# rt1_handle.net
KiCad netlist of a schematic drawn in EAGLE
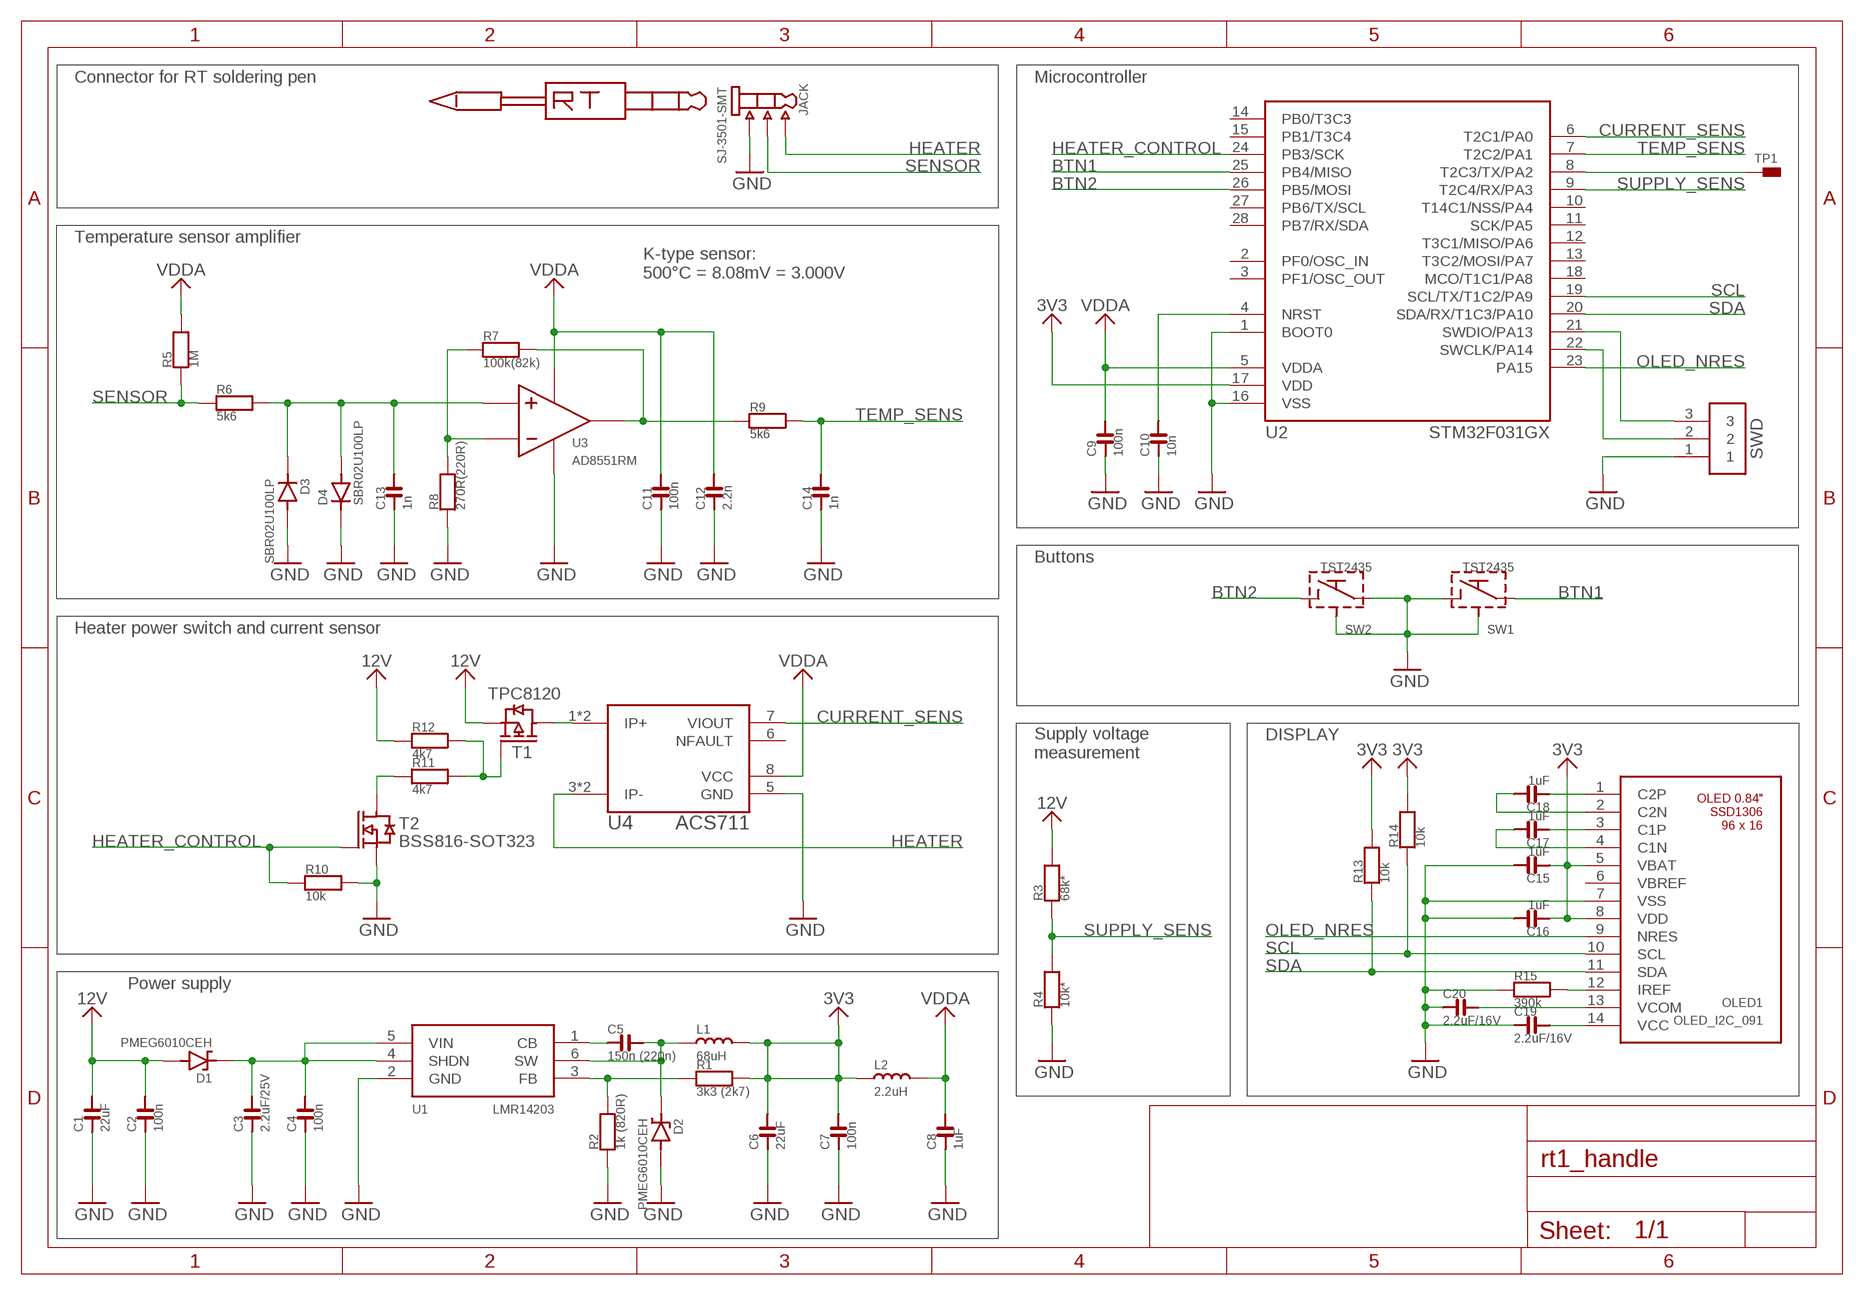
[diagram p0: schematic, sheet 1]

(export (version "E")
  (design (tool "Eeschema 10.0.6"))
  (components
    (comp (ref "C1")
      (value "22uF")
      (footprint "eagle-import:1206")
      (libsource (lib "eagle-import") (part "C1206"))
    )
    (comp (ref "C2")
      (value "100n")
      (footprint "eagle-import:0402")
      (libsource (lib "eagle-import") (part "C0402"))
    )
    (comp (ref "C3")
      (value "2.2uF/25V")
      (footprint "eagle-import:0805")
      (libsource (lib "eagle-import") (part "C0805"))
    )
    (comp (ref "C4")
      (value "100n")
      (footprint "eagle-import:0402")
      (libsource (lib "eagle-import") (part "C0402"))
    )
    (comp (ref "C5")
      (value "150n (220n)")
      (footprint "eagle-import:0402")
      (libsource (lib "eagle-import") (part "C0402"))
    )
    (comp (ref "C6")
      (value "22uF")
      (footprint "eagle-import:0805")
      (libsource (lib "eagle-import") (part "C0805"))
    )
    (comp (ref "C7")
      (value "100n")
      (footprint "eagle-import:0402")
      (libsource (lib "eagle-import") (part "C0402"))
    )
    (comp (ref "C8")
      (value "1uF")
      (footprint "eagle-import:0603")
      (libsource (lib "eagle-import") (part "C0603"))
    )
    (comp (ref "C9")
      (value "100n")
      (footprint "eagle-import:0402")
      (libsource (lib "eagle-import") (part "C0402"))
    )
    (comp (ref "C10")
      (value "10n")
      (footprint "eagle-import:0402")
      (libsource (lib "eagle-import") (part "C0402"))
    )
    (comp (ref "C11")
      (value "100n")
      (footprint "eagle-import:0402")
      (libsource (lib "eagle-import") (part "C0402"))
    )
    (comp (ref "C12")
      (value "2.2n")
      (footprint "eagle-import:0603")
      (libsource (lib "eagle-import") (part "C0603"))
    )
    (comp (ref "C13")
      (value "1n")
      (footprint "eagle-import:0402")
      (libsource (lib "eagle-import") (part "C0402"))
    )
    (comp (ref "C14")
      (value "1n")
      (footprint "eagle-import:0402")
      (libsource (lib "eagle-import") (part "C0402"))
    )
    (comp (ref "C15")
      (value "1uF")
      (footprint "eagle-import:0603")
      (libsource (lib "eagle-import") (part "C0603"))
    )
    (comp (ref "C16")
      (value "1uF")
      (footprint "eagle-import:0603")
      (libsource (lib "eagle-import") (part "C0603"))
    )
    (comp (ref "C17")
      (value "1uF")
      (footprint "eagle-import:0603")
      (libsource (lib "eagle-import") (part "C0603"))
    )
    (comp (ref "C18")
      (value "1uF")
      (footprint "eagle-import:0603")
      (libsource (lib "eagle-import") (part "C0603"))
    )
    (comp (ref "C19")
      (value "2.2uF/16V")
      (footprint "eagle-import:0603")
      (libsource (lib "eagle-import") (part "C0603"))
    )
    (comp (ref "C20")
      (value "2.2uF/16V")
      (footprint "eagle-import:0603")
      (libsource (lib "eagle-import") (part "C0603"))
    )
    (comp (ref "D1")
      (value "PMEG6010CEH")
      (footprint "eagle-import:SOD123F")
      (libsource (lib "eagle-import") (part "PMEG6010CEH"))
    )
    (comp (ref "D2")
      (value "PMEG6010CEH")
      (footprint "eagle-import:SOD123F")
      (libsource (lib "eagle-import") (part "PMEG6010CEH"))
    )
    (comp (ref "D3")
      (value "SBR02U100LP")
      (footprint "eagle-import:DFN1006")
      (libsource (lib "eagle-import") (part "SBR02U100LP"))
    )
    (comp (ref "D4")
      (value "SBR02U100LP")
      (footprint "eagle-import:DFN1006")
      (libsource (lib "eagle-import") (part "SBR02U100LP"))
    )
    (comp (ref "JACK")
      (value "SJ-3501-SMT")
      (footprint "eagle-import:SJ-3501-SMT")
      (libsource (lib "eagle-import") (part "SJ-3501-SMT"))
    )
    (comp (ref "L1")
      (value "68uH")
      (footprint "eagle-import:1717")
      (libsource (lib "eagle-import") (part "L1717"))
    )
    (comp (ref "L2")
      (value "2.2uH")
      (footprint "eagle-import:0805")
      (libsource (lib "eagle-import") (part "L0805"))
    )
    (comp (ref "OLED1")
      (value "OLED_I2C_091")
      (footprint "eagle-import:OLED_I2C_091")
      (libsource (lib "eagle-import") (part "OLED_I2C_091"))
    )
    (comp (ref "R1")
      (value "3k3 (2k7)")
      (footprint "eagle-import:0402")
      (libsource (lib "eagle-import") (part "R0402"))
    )
    (comp (ref "R2")
      (value "1k (820R)")
      (footprint "eagle-import:0402")
      (libsource (lib "eagle-import") (part "R0402"))
    )
    (comp (ref "R3")
      (value "68k*")
      (footprint "eagle-import:0402")
      (libsource (lib "eagle-import") (part "R0402"))
    )
    (comp (ref "R4")
      (value "10k*")
      (footprint "eagle-import:0402")
      (libsource (lib "eagle-import") (part "R0402"))
    )
    (comp (ref "R5")
      (value "1M")
      (footprint "eagle-import:0402")
      (libsource (lib "eagle-import") (part "R0402"))
    )
    (comp (ref "R6")
      (value "5k6")
      (footprint "eagle-import:0402")
      (libsource (lib "eagle-import") (part "R0402"))
    )
    (comp (ref "R7")
      (value "100k(82k)")
      (footprint "eagle-import:0402")
      (libsource (lib "eagle-import") (part "R0402"))
    )
    (comp (ref "R8")
      (value "270R(220R)")
      (footprint "eagle-import:0402")
      (libsource (lib "eagle-import") (part "R0402"))
    )
    (comp (ref "R9")
      (value "5k6")
      (footprint "eagle-import:0402")
      (libsource (lib "eagle-import") (part "R0402"))
    )
    (comp (ref "R10")
      (value "10k")
      (footprint "eagle-import:0402")
      (libsource (lib "eagle-import") (part "R0402"))
    )
    (comp (ref "R11")
      (value "4k7")
      (footprint "eagle-import:0402")
      (libsource (lib "eagle-import") (part "R0402"))
    )
    (comp (ref "R12")
      (value "4k7")
      (footprint "eagle-import:0402")
      (libsource (lib "eagle-import") (part "R0402"))
    )
    (comp (ref "R13")
      (value "10k")
      (footprint "eagle-import:0402")
      (libsource (lib "eagle-import") (part "R0402"))
    )
    (comp (ref "R14")
      (value "10k")
      (footprint "eagle-import:0402")
      (libsource (lib "eagle-import") (part "R0402"))
    )
    (comp (ref "R15")
      (value "390k")
      (footprint "eagle-import:0402")
      (libsource (lib "eagle-import") (part "R0402"))
    )
    (comp (ref "RT")
      (value "RT-1")
      (footprint "eagle-import:RT-1")
      (libsource (lib "eagle-import") (part "RT-1"))
    )
    (comp (ref "SW1")
      (value "TST2435")
      (footprint "eagle-import:TST2435")
      (libsource (lib "eagle-import") (part "TST2435"))
    )
    (comp (ref "SW2")
      (value "TST2435")
      (footprint "eagle-import:TST2435")
      (libsource (lib "eagle-import") (part "TST2435"))
    )
    (comp (ref "SWD")
      (value "PINHEAD1X3X")
      (footprint "eagle-import:PIN1X3")
      (libsource (lib "eagle-import") (part "PINHEAD1X3X"))
    )
    (comp (ref "T1")
      (value "TPC8120")
      (footprint "eagle-import:SOIC8")
      (libsource (lib "eagle-import") (part "TPC8120"))
    )
    (comp (ref "T2")
      (value "BSS816-SOT323")
      (footprint "eagle-import:SOT23")
      (libsource (lib "eagle-import") (part "IRLML2502"))
    )
    (comp (ref "TP1")
      (value "TEST_PAD15X60")
      (footprint "eagle-import:SMD_15_60")
      (libsource (lib "eagle-import") (part "TEST_PAD15X60"))
    )
    (comp (ref "U1")
      (value "LMR14203")
      (footprint "eagle-import:SOT23-6")
      (libsource (lib "eagle-import") (part "LMR14203"))
    )
    (comp (ref "U2")
      (value "STM32F031GX")
      (footprint "eagle-import:UFQFPN28")
      (libsource (lib "eagle-import") (part "STM32F031GX"))
    )
    (comp (ref "U3")
      (value "AD8551RM")
      (footprint "eagle-import:MSOP8")
      (libsource (lib "eagle-import") (part "AD8551RM"))
    )
    (comp (ref "U4")
      (value "ACS711")
      (footprint "eagle-import:SOIC8")
      (libsource (lib "eagle-import") (part "ACS711"))
    )
  )
  (nets
    (net (code "1") (name "/BTN1") (class "Default")
      (node (ref "SW1") (pin "1") (pinfunction "1_1") (pintype "passive"))
      (node (ref "U2") (pin "25") (pinfunction "PB4/MISO_25") (pintype "bidirectional"))
    )
    (net (code "2") (name "/BTN2") (class "Default")
      (node (ref "SW2") (pin "2") (pinfunction "2_2") (pintype "passive"))
      (node (ref "U2") (pin "26") (pinfunction "PB5/MOSI_26") (pintype "bidirectional"))
    )
    (net (code "3") (name "/CURRENT_SENS") (class "Default")
      (node (ref "U2") (pin "6") (pinfunction "T2C1/PA0_6") (pintype "bidirectional"))
      (node (ref "U4") (pin "7") (pinfunction "VIOUT_7") (pintype "bidirectional"))
    )
    (net (code "4") (name "/HEATER") (class "Default")
      (node (ref "JACK") (pin "2") (pinfunction "2_2") (pintype "bidirectional"))
      (node (ref "JACK") (pin "4") (pinfunction "2_4") (pintype "bidirectional"))
      (node (ref "U4") (pin "3") (pinfunction "IP-_3") (pintype "bidirectional"))
      (node (ref "U4") (pin "4") (pinfunction "IP-_4") (pintype "bidirectional"))
    )
    (net (code "5") (name "/HEATER_CONTROL") (class "Default")
      (node (ref "R10") (pin "1") (pinfunction "1_1") (pintype "passive"))
      (node (ref "T2") (pin "1") (pinfunction "G_1") (pintype "bidirectional"))
      (node (ref "U2") (pin "24") (pinfunction "PB3/SCK_24") (pintype "bidirectional"))
    )
    (net (code "6") (name "/OLED_NRES") (class "Default")
      (node (ref "OLED1") (pin "9") (pinfunction "NRES_9") (pintype "input"))
      (node (ref "U2") (pin "23") (pinfunction "PA15_23") (pintype "bidirectional"))
    )
    (net (code "7") (name "/SCL") (class "Default")
      (node (ref "OLED1") (pin "10") (pinfunction "SCL_10") (pintype "input"))
      (node (ref "R14") (pin "1") (pinfunction "1_1") (pintype "passive"))
      (node (ref "U2") (pin "19") (pinfunction "SCL/TX/T1C2/PA9_19") (pintype "bidirectional"))
    )
    (net (code "8") (name "/SDA") (class "Default")
      (node (ref "OLED1") (pin "11") (pinfunction "SDA_11") (pintype "input"))
      (node (ref "R13") (pin "1") (pinfunction "1_1") (pintype "passive"))
      (node (ref "U2") (pin "20") (pinfunction "SDA/RX/T1C3/PA10_20") (pintype "bidirectional"))
    )
    (net (code "9") (name "/SENSOR") (class "Default")
      (node (ref "JACK") (pin "3") (pinfunction "3_3") (pintype "bidirectional"))
      (node (ref "R5") (pin "1") (pinfunction "1_1") (pintype "passive"))
      (node (ref "R6") (pin "1") (pinfunction "1_1") (pintype "passive"))
    )
    (net (code "10") (name "/SUPPLY_SENS") (class "Default")
      (node (ref "R3") (pin "1") (pinfunction "1_1") (pintype "passive"))
      (node (ref "R4") (pin "2") (pinfunction "2_2") (pintype "passive"))
      (node (ref "U2") (pin "9") (pinfunction "T2C4/RX/PA3_9") (pintype "bidirectional"))
    )
    (net (code "11") (name "/TEMP_SENS") (class "Default")
      (node (ref "C14") (pin "2") (pinfunction "2_2") (pintype "passive"))
      (node (ref "R9") (pin "2") (pinfunction "2_2") (pintype "passive"))
      (node (ref "U2") (pin "7") (pinfunction "T2C2/PA1_7") (pintype "bidirectional"))
    )
    (net (code "12") (name "3V3") (class "Default")
      (node (ref "C15") (pin "1") (pinfunction "1_1") (pintype "passive"))
      (node (ref "C16") (pin "1") (pinfunction "1_1") (pintype "passive"))
      (node (ref "C6") (pin "2") (pinfunction "2_2") (pintype "passive"))
      (node (ref "C7") (pin "2") (pinfunction "2_2") (pintype "passive"))
      (node (ref "L1") (pin "2") (pinfunction "2_2") (pintype "passive"))
      (node (ref "L2") (pin "1") (pinfunction "1_1") (pintype "passive"))
      (node (ref "OLED1") (pin "5") (pinfunction "VBAT_5") (pintype "power_in"))
      (node (ref "OLED1") (pin "8") (pinfunction "VDD_8") (pintype "power_in"))
      (node (ref "R1") (pin "2") (pinfunction "2_2") (pintype "passive"))
      (node (ref "R13") (pin "2") (pinfunction "2_2") (pintype "passive"))
      (node (ref "R14") (pin "2") (pinfunction "2_2") (pintype "passive"))
      (node (ref "U2") (pin "17") (pinfunction "VDD_17") (pintype "power_in"))
    )
    (net (code "13") (name "12V") (class "Default")
      (node (ref "C1") (pin "2") (pinfunction "2_2") (pintype "passive"))
      (node (ref "C2") (pin "2") (pinfunction "2_2") (pintype "passive"))
      (node (ref "D1") (pin "A") (pinfunction "A_A") (pintype "passive"))
      (node (ref "R12") (pin "1") (pinfunction "1_1") (pintype "passive"))
      (node (ref "R3") (pin "2") (pinfunction "2_2") (pintype "passive"))
      (node (ref "T1") (pin "1") (pinfunction "S_1") (pintype "bidirectional"))
      (node (ref "T1") (pin "2") (pinfunction "S_2") (pintype "bidirectional"))
      (node (ref "T1") (pin "3") (pinfunction "S_3") (pintype "bidirectional"))
    )
    (net (code "14") (name "GND") (class "Default")
      (node (ref "C1") (pin "1") (pinfunction "1_1") (pintype "passive"))
      (node (ref "C10") (pin "1") (pinfunction "1_1") (pintype "passive"))
      (node (ref "C11") (pin "1") (pinfunction "1_1") (pintype "passive"))
      (node (ref "C12") (pin "1") (pinfunction "1_1") (pintype "passive"))
      (node (ref "C13") (pin "1") (pinfunction "1_1") (pintype "passive"))
      (node (ref "C14") (pin "1") (pinfunction "1_1") (pintype "passive"))
      (node (ref "C15") (pin "2") (pinfunction "2_2") (pintype "passive"))
      (node (ref "C16") (pin "2") (pinfunction "2_2") (pintype "passive"))
      (node (ref "C19") (pin "1") (pinfunction "1_1") (pintype "passive"))
      (node (ref "C2") (pin "1") (pinfunction "1_1") (pintype "passive"))
      (node (ref "C20") (pin "1") (pinfunction "1_1") (pintype "passive"))
      (node (ref "C3") (pin "1") (pinfunction "1_1") (pintype "passive"))
      (node (ref "C4") (pin "1") (pinfunction "1_1") (pintype "passive"))
      (node (ref "C6") (pin "1") (pinfunction "1_1") (pintype "passive"))
      (node (ref "C7") (pin "1") (pinfunction "1_1") (pintype "passive"))
      (node (ref "C8") (pin "1") (pinfunction "1_1") (pintype "passive"))
      (node (ref "C9") (pin "1") (pinfunction "1_1") (pintype "passive"))
      (node (ref "D2") (pin "A") (pinfunction "A_A") (pintype "passive"))
      (node (ref "D3") (pin "A") (pinfunction "A_A") (pintype "passive"))
      (node (ref "D4") (pin "C") (pinfunction "C_C") (pintype "passive"))
      (node (ref "JACK") (pin "1") (pinfunction "1_1") (pintype "bidirectional"))
      (node (ref "JACK") (pin "5") (pinfunction "1_5") (pintype "bidirectional"))
      (node (ref "OLED1") (pin "7") (pinfunction "VSS_7") (pintype "power_in"))
      (node (ref "R10") (pin "2") (pinfunction "2_2") (pintype "passive"))
      (node (ref "R15") (pin "1") (pinfunction "1_1") (pintype "passive"))
      (node (ref "R2") (pin "1") (pinfunction "1_1") (pintype "passive"))
      (node (ref "R4") (pin "1") (pinfunction "1_1") (pintype "passive"))
      (node (ref "R8") (pin "1") (pinfunction "1_1") (pintype "passive"))
      (node (ref "SW1") (pin "2") (pinfunction "2_2") (pintype "passive"))
      (node (ref "SW1") (pin "EP1") (pinfunction "SHIELD_EP1") (pintype "passive"))
      (node (ref "SW1") (pin "EP2") (pinfunction "SHIELD_EP2") (pintype "passive"))
      (node (ref "SW2") (pin "1") (pinfunction "1_1") (pintype "passive"))
      (node (ref "SW2") (pin "EP1") (pinfunction "SHIELD_EP1") (pintype "passive"))
      (node (ref "SW2") (pin "EP2") (pinfunction "SHIELD_EP2") (pintype "passive"))
      (node (ref "SWD") (pin "1") (pinfunction "1_1") (pintype "bidirectional"))
      (node (ref "T2") (pin "2") (pinfunction "S_2") (pintype "bidirectional"))
      (node (ref "U1") (pin "2") (pinfunction "GND_2") (pintype "power_in"))
      (node (ref "U2") (pin "1") (pinfunction "BOOT0_1") (pintype "input"))
      (node (ref "U2") (pin "16") (pinfunction "VSS_16") (pintype "power_in"))
      (node (ref "U3") (pin "4") (pinfunction "V-_4") (pintype "power_in"))
      (node (ref "U4") (pin "5") (pinfunction "GND_5") (pintype "power_in"))
    )
    (net (code "15") (name "Net-(OLED1-C1N)") (class "Default")
      (node (ref "C17") (pin "2") (pinfunction "2_2") (pintype "passive"))
      (node (ref "OLED1") (pin "4") (pinfunction "C1N_4") (pintype "passive"))
    )
    (net (code "16") (name "Net-(OLED1-C1P)") (class "Default")
      (node (ref "C17") (pin "1") (pinfunction "1_1") (pintype "passive"))
      (node (ref "OLED1") (pin "3") (pinfunction "C1P_3") (pintype "passive"))
    )
    (net (code "17") (name "Net-(OLED1-C2N)") (class "Default")
      (node (ref "C18") (pin "2") (pinfunction "2_2") (pintype "passive"))
      (node (ref "OLED1") (pin "2") (pinfunction "C2N_2") (pintype "passive"))
    )
    (net (code "18") (name "Net-(OLED1-C2P)") (class "Default")
      (node (ref "C18") (pin "1") (pinfunction "1_1") (pintype "passive"))
      (node (ref "OLED1") (pin "1") (pinfunction "C2P_1") (pintype "passive"))
    )
    (net (code "19") (name "Net-(OLED1-IREF)") (class "Default")
      (node (ref "OLED1") (pin "12") (pinfunction "IREF_12") (pintype "passive"))
      (node (ref "R15") (pin "2") (pinfunction "2_2") (pintype "passive"))
    )
    (net (code "20") (name "Net-(OLED1-VCC)") (class "Default")
      (node (ref "C19") (pin "2") (pinfunction "2_2") (pintype "passive"))
      (node (ref "OLED1") (pin "14") (pinfunction "VCC_14") (pintype "power_in"))
    )
    (net (code "21") (name "Net-(OLED1-VCOM)") (class "Default")
      (node (ref "C20") (pin "2") (pinfunction "2_2") (pintype "passive"))
      (node (ref "OLED1") (pin "13") (pinfunction "VCOM_13") (pintype "passive"))
    )
    (net (code "22") (name "Net-(T1-D-Pad5)") (class "Default")
      (node (ref "T1") (pin "5") (pinfunction "D_5") (pintype "bidirectional"))
      (node (ref "T1") (pin "6") (pinfunction "D_6") (pintype "bidirectional"))
      (node (ref "T1") (pin "7") (pinfunction "D_7") (pintype "bidirectional"))
      (node (ref "T1") (pin "8") (pinfunction "D_8") (pintype "bidirectional"))
      (node (ref "U4") (pin "1") (pinfunction "IP+_1") (pintype "bidirectional"))
      (node (ref "U4") (pin "2") (pinfunction "IP+_2") (pintype "bidirectional"))
    )
    (net (code "23") (name "Net-(T1-G)") (class "Default")
      (node (ref "R11") (pin "2") (pinfunction "2_2") (pintype "passive"))
      (node (ref "R12") (pin "2") (pinfunction "2_2") (pintype "passive"))
      (node (ref "T1") (pin "4") (pinfunction "G_4") (pintype "bidirectional"))
    )
    (net (code "24") (name "Net-(T2-D)") (class "Default")
      (node (ref "R11") (pin "1") (pinfunction "1_1") (pintype "passive"))
      (node (ref "T2") (pin "3") (pinfunction "D_3") (pintype "bidirectional"))
    )
    (net (code "25") (name "Net-(U1-CB)") (class "Default")
      (node (ref "C5") (pin "1") (pinfunction "1_1") (pintype "passive"))
      (node (ref "U1") (pin "1") (pinfunction "CB_1") (pintype "passive"))
    )
    (net (code "26") (name "Net-(U1-FB)") (class "Default")
      (node (ref "R1") (pin "1") (pinfunction "1_1") (pintype "passive"))
      (node (ref "R2") (pin "2") (pinfunction "2_2") (pintype "passive"))
      (node (ref "U1") (pin "3") (pinfunction "FB_3") (pintype "input"))
    )
    (net (code "27") (name "Net-(U1-SHDN)") (class "Default")
      (node (ref "C3") (pin "2") (pinfunction "2_2") (pintype "passive"))
      (node (ref "C4") (pin "2") (pinfunction "2_2") (pintype "passive"))
      (node (ref "D1") (pin "C") (pinfunction "C_C") (pintype "passive"))
      (node (ref "U1") (pin "4") (pinfunction "SHDN_4") (pintype "input"))
      (node (ref "U1") (pin "5") (pinfunction "VIN_5") (pintype "power_in"))
    )
    (net (code "28") (name "Net-(U1-SW)") (class "Default")
      (node (ref "C5") (pin "2") (pinfunction "2_2") (pintype "passive"))
      (node (ref "D2") (pin "C") (pinfunction "C_C") (pintype "passive"))
      (node (ref "L1") (pin "1") (pinfunction "1_1") (pintype "passive"))
      (node (ref "U1") (pin "6") (pinfunction "SW_6") (pintype "output"))
    )
    (net (code "29") (name "Net-(U2-NRST)") (class "Default")
      (node (ref "C10") (pin "2") (pinfunction "2_2") (pintype "passive"))
      (node (ref "U2") (pin "4") (pinfunction "NRST_4") (pintype "input"))
    )
    (net (code "30") (name "Net-(U2-SWCLK{slash}PA14)") (class "Default")
      (node (ref "SWD") (pin "2") (pinfunction "2_2") (pintype "bidirectional"))
      (node (ref "U2") (pin "22") (pinfunction "SWCLK/PA14_22") (pintype "bidirectional"))
    )
    (net (code "31") (name "Net-(U2-SWDIO{slash}PA13)") (class "Default")
      (node (ref "SWD") (pin "3") (pinfunction "3_3") (pintype "bidirectional"))
      (node (ref "U2") (pin "21") (pinfunction "SWDIO/PA13_21") (pintype "bidirectional"))
    )
    (net (code "32") (name "Net-(U2-T2C3{slash}TX{slash}PA2)") (class "Default")
      (node (ref "TP1") (pin "TP") (pinfunction "TP_TP") (pintype "bidirectional"))
      (node (ref "U2") (pin "8") (pinfunction "T2C3/TX/PA2_8") (pintype "bidirectional"))
    )
    (net (code "33") (name "Net-(U3-IN+)") (class "Default")
      (node (ref "C13") (pin "2") (pinfunction "2_2") (pintype "passive"))
      (node (ref "D3") (pin "C") (pinfunction "C_C") (pintype "passive"))
      (node (ref "D4") (pin "A") (pinfunction "A_A") (pintype "passive"))
      (node (ref "R6") (pin "2") (pinfunction "2_2") (pintype "passive"))
      (node (ref "U3") (pin "3") (pinfunction "IN+_3") (pintype "input"))
    )
    (net (code "34") (name "Net-(U3-IN-)") (class "Default")
      (node (ref "R7") (pin "1") (pinfunction "1_1") (pintype "passive"))
      (node (ref "R8") (pin "2") (pinfunction "2_2") (pintype "passive"))
      (node (ref "U3") (pin "2") (pinfunction "IN-_2") (pintype "input"))
    )
    (net (code "35") (name "Net-(U3-OUT)") (class "Default")
      (node (ref "R7") (pin "2") (pinfunction "2_2") (pintype "passive"))
      (node (ref "R9") (pin "1") (pinfunction "1_1") (pintype "passive"))
      (node (ref "U3") (pin "6") (pinfunction "OUT_6") (pintype "output"))
    )
    (net (code "36") (name "VDDA") (class "Default")
      (node (ref "C11") (pin "2") (pinfunction "2_2") (pintype "passive"))
      (node (ref "C12") (pin "2") (pinfunction "2_2") (pintype "passive"))
      (node (ref "C8") (pin "2") (pinfunction "2_2") (pintype "passive"))
      (node (ref "C9") (pin "2") (pinfunction "2_2") (pintype "passive"))
      (node (ref "L2") (pin "2") (pinfunction "2_2") (pintype "passive"))
      (node (ref "R5") (pin "2") (pinfunction "2_2") (pintype "passive"))
      (node (ref "U2") (pin "5") (pinfunction "VDDA_5") (pintype "power_in"))
      (node (ref "U3") (pin "7") (pinfunction "V+_7") (pintype "power_in"))
      (node (ref "U4") (pin "8") (pinfunction "VCC_8") (pintype "power_in"))
    )
    (net (code "37") (name "unconnected-(OLED1-VBREF-Pad6)") (class "Default")
      (node (ref "OLED1") (pin "6") (pinfunction "VBREF_6") (pintype "passive"))
    )
    (net (code "38") (name "unconnected-(U2-MCO{slash}T1C1{slash}PA8-Pad18)") (class "Default")
      (node (ref "U2") (pin "18") (pinfunction "MCO/T1C1/PA8_18") (pintype "bidirectional"))
    )
    (net (code "39") (name "unconnected-(U2-PB0{slash}T3C3-Pad14)") (class "Default")
      (node (ref "U2") (pin "14") (pinfunction "PB0/T3C3_14") (pintype "bidirectional"))
    )
    (net (code "40") (name "unconnected-(U2-PB1{slash}T3C4-Pad15)") (class "Default")
      (node (ref "U2") (pin "15") (pinfunction "PB1/T3C4_15") (pintype "bidirectional"))
    )
    (net (code "41") (name "unconnected-(U2-PB6{slash}TX{slash}SCL-Pad27)") (class "Default")
      (node (ref "U2") (pin "27") (pinfunction "PB6/TX/SCL_27") (pintype "bidirectional"))
    )
    (net (code "42") (name "unconnected-(U2-PB7{slash}RX{slash}SDA-Pad28)") (class "Default")
      (node (ref "U2") (pin "28") (pinfunction "PB7/RX/SDA_28") (pintype "bidirectional"))
    )
    (net (code "43") (name "unconnected-(U2-PF0{slash}OSC_IN-Pad2)") (class "Default")
      (node (ref "U2") (pin "2") (pinfunction "PF0/OSC_IN_2") (pintype "bidirectional"))
    )
    (net (code "44") (name "unconnected-(U2-PF1{slash}OSC_OUT-Pad3)") (class "Default")
      (node (ref "U2") (pin "3") (pinfunction "PF1/OSC_OUT_3") (pintype "bidirectional"))
    )
    (net (code "45") (name "unconnected-(U2-SCK{slash}PA5-Pad11)") (class "Default")
      (node (ref "U2") (pin "11") (pinfunction "SCK/PA5_11") (pintype "bidirectional"))
    )
    (net (code "46") (name "unconnected-(U2-T3C1{slash}MISO{slash}PA6-Pad12)") (class "Default")
      (node (ref "U2") (pin "12") (pinfunction "T3C1/MISO/PA6_12") (pintype "bidirectional"))
    )
    (net (code "47") (name "unconnected-(U2-T3C2{slash}MOSI{slash}PA7-Pad13)") (class "Default")
      (node (ref "U2") (pin "13") (pinfunction "T3C2/MOSI/PA7_13") (pintype "bidirectional"))
    )
    (net (code "48") (name "unconnected-(U2-T14C1{slash}NSS{slash}PA4-Pad10)") (class "Default")
      (node (ref "U2") (pin "10") (pinfunction "T14C1/NSS/PA4_10") (pintype "bidirectional"))
    )
    (net (code "49") (name "unconnected-(U4-NFAULT-Pad6)") (class "Default")
      (node (ref "U4") (pin "6") (pinfunction "NFAULT_6") (pintype "open_collector"))
    )
  )
)
